# Balancing_FETs.net
KiCad netlist of a schematic drawn in Altium Designer
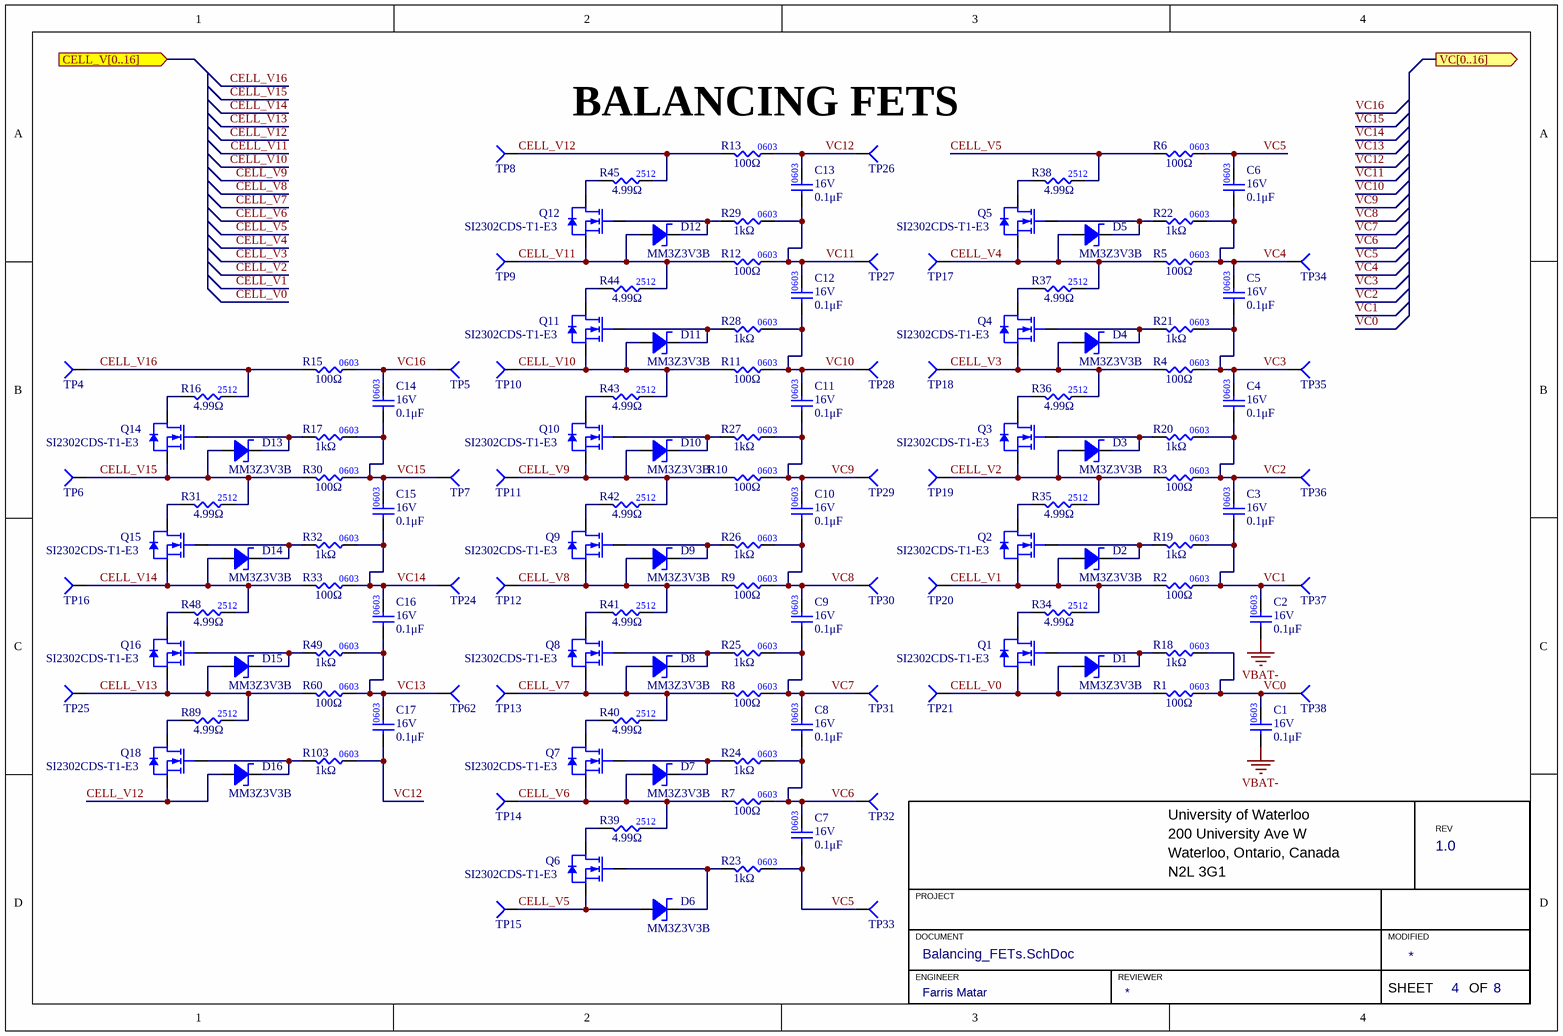
[diagram p0: Balancing_FETs.SchDoc]

(export (version "E")
  (design (tool "Eeschema 10.0.6"))
  (components
    (comp (ref "C1")
      (value "0.1μF")
      (footprint "CAP0603")
      (description "CAP CER 0.1UF 16V X7R 0603")
      (fields (field (name "VOLTAGE RATING") "16V") (field (name "Comment") "CAP_0.1uF_16V_0603"))
      (libsource (lib "Personal_Schematic_Library_2022") (part "CAP_0.1uF_16V_0603"))
    )
    (comp (ref "C2")
      (value "0.1μF")
      (footprint "CAP0603")
      (description "CAP CER 0.1UF 16V X7R 0603")
      (fields (field (name "VOLTAGE RATING") "16V") (field (name "Comment") "CAP_0.1uF_16V_0603"))
      (libsource (lib "Personal_Schematic_Library_2022") (part "CAP_0.1uF_16V_0603"))
    )
    (comp (ref "C3")
      (value "0.1μF")
      (footprint "CAP0603")
      (description "CAP CER 0.1UF 16V X7R 0603")
      (fields (field (name "VOLTAGE RATING") "16V") (field (name "Comment") "CAP_0.1uF_16V_0603"))
      (libsource (lib "Personal_Schematic_Library_2022") (part "CAP_0.1uF_16V_0603"))
    )
    (comp (ref "C4")
      (value "0.1μF")
      (footprint "CAP0603")
      (description "CAP CER 0.1UF 16V X7R 0603")
      (fields (field (name "VOLTAGE RATING") "16V") (field (name "Comment") "CAP_0.1uF_16V_0603"))
      (libsource (lib "Personal_Schematic_Library_2022") (part "CAP_0.1uF_16V_0603"))
    )
    (comp (ref "C5")
      (value "0.1μF")
      (footprint "CAP0603")
      (description "CAP CER 0.1UF 16V X7R 0603")
      (fields (field (name "VOLTAGE RATING") "16V") (field (name "Comment") "CAP_0.1uF_16V_0603"))
      (libsource (lib "Personal_Schematic_Library_2022") (part "CAP_0.1uF_16V_0603"))
    )
    (comp (ref "C6")
      (value "0.1μF")
      (footprint "CAP0603")
      (description "CAP CER 0.1UF 16V X7R 0603")
      (fields (field (name "VOLTAGE RATING") "16V") (field (name "Comment") "CAP_0.1uF_16V_0603"))
      (libsource (lib "Personal_Schematic_Library_2022") (part "CAP_0.1uF_16V_0603"))
    )
    (comp (ref "C7")
      (value "0.1μF")
      (footprint "CAP0603")
      (description "CAP CER 0.1UF 16V X7R 0603")
      (fields (field (name "VOLTAGE RATING") "16V") (field (name "Comment") "CAP_0.1uF_16V_0603"))
      (libsource (lib "Personal_Schematic_Library_2022") (part "CAP_0.1uF_16V_0603"))
    )
    (comp (ref "C8")
      (value "0.1μF")
      (footprint "CAP0603")
      (description "CAP CER 0.1UF 16V X7R 0603")
      (fields (field (name "VOLTAGE RATING") "16V") (field (name "Comment") "CAP_0.1uF_16V_0603"))
      (libsource (lib "Personal_Schematic_Library_2022") (part "CAP_0.1uF_16V_0603"))
    )
    (comp (ref "C9")
      (value "0.1μF")
      (footprint "CAP0603")
      (description "CAP CER 0.1UF 16V X7R 0603")
      (fields (field (name "VOLTAGE RATING") "16V") (field (name "Comment") "CAP_0.1uF_16V_0603"))
      (libsource (lib "Personal_Schematic_Library_2022") (part "CAP_0.1uF_16V_0603"))
    )
    (comp (ref "C10")
      (value "0.1μF")
      (footprint "CAP0603")
      (description "CAP CER 0.1UF 16V X7R 0603")
      (fields (field (name "VOLTAGE RATING") "16V") (field (name "Comment") "CAP_0.1uF_16V_0603"))
      (libsource (lib "Personal_Schematic_Library_2022") (part "CAP_0.1uF_16V_0603"))
    )
    (comp (ref "C11")
      (value "0.1μF")
      (footprint "CAP0603")
      (description "CAP CER 0.1UF 16V X7R 0603")
      (fields (field (name "VOLTAGE RATING") "16V") (field (name "Comment") "CAP_0.1uF_16V_0603"))
      (libsource (lib "Personal_Schematic_Library_2022") (part "CAP_0.1uF_16V_0603"))
    )
    (comp (ref "C12")
      (value "0.1μF")
      (footprint "CAP0603")
      (description "CAP CER 0.1UF 16V X7R 0603")
      (fields (field (name "VOLTAGE RATING") "16V") (field (name "Comment") "CAP_0.1uF_16V_0603"))
      (libsource (lib "Personal_Schematic_Library_2022") (part "CAP_0.1uF_16V_0603"))
    )
    (comp (ref "C13")
      (value "0.1μF")
      (footprint "CAP0603")
      (description "CAP CER 0.1UF 16V X7R 0603")
      (fields (field (name "VOLTAGE RATING") "16V") (field (name "Comment") "CAP_0.1uF_16V_0603"))
      (libsource (lib "Personal_Schematic_Library_2022") (part "CAP_0.1uF_16V_0603"))
    )
    (comp (ref "C14")
      (value "0.1μF")
      (footprint "CAP0603")
      (description "CAP CER 0.1UF 16V X7R 0603")
      (fields (field (name "VOLTAGE RATING") "16V") (field (name "Comment") "CAP_0.1uF_16V_0603"))
      (libsource (lib "Personal_Schematic_Library_2022") (part "CAP_0.1uF_16V_0603"))
    )
    (comp (ref "C15")
      (value "0.1μF")
      (footprint "CAP0603")
      (description "CAP CER 0.1UF 16V X7R 0603")
      (fields (field (name "VOLTAGE RATING") "16V") (field (name "Comment") "CAP_0.1uF_16V_0603"))
      (libsource (lib "Personal_Schematic_Library_2022") (part "CAP_0.1uF_16V_0603"))
    )
    (comp (ref "C16")
      (value "0.1μF")
      (footprint "CAP0603")
      (description "CAP CER 0.1UF 16V X7R 0603")
      (fields (field (name "VOLTAGE RATING") "16V") (field (name "Comment") "CAP_0.1uF_16V_0603"))
      (libsource (lib "Personal_Schematic_Library_2022") (part "CAP_0.1uF_16V_0603"))
    )
    (comp (ref "C17")
      (value "0.1μF")
      (footprint "CAP0603")
      (description "CAP CER 0.1UF 16V X7R 0603")
      (fields (field (name "VOLTAGE RATING") "16V") (field (name "Comment") "CAP_0.1uF_16V_0603"))
      (libsource (lib "Personal_Schematic_Library_2022") (part "CAP_0.1uF_16V_0603"))
    )
    (comp (ref "D1")
      (value "DIO_ZENER_3V3")
      (footprint "DIO_ZENER_3V3")
      (description "DIODE ZENER 3.3V 200mW SOD323F")
      (fields (field (name "MANUFACTURER PART NUMBER 1") "MM3Z3V3B"))
      (libsource (lib "Personal_Schematic_Library_2022") (part "DIO_ZENER_3V3"))
    )
    (comp (ref "D2")
      (value "DIO_ZENER_3V3")
      (footprint "DIO_ZENER_3V3")
      (description "DIODE ZENER 3.3V 200mW SOD323F")
      (fields (field (name "MANUFACTURER PART NUMBER 1") "MM3Z3V3B"))
      (libsource (lib "Personal_Schematic_Library_2022") (part "DIO_ZENER_3V3"))
    )
    (comp (ref "D3")
      (value "DIO_ZENER_3V3")
      (footprint "DIO_ZENER_3V3")
      (description "DIODE ZENER 3.3V 200mW SOD323F")
      (fields (field (name "MANUFACTURER PART NUMBER 1") "MM3Z3V3B"))
      (libsource (lib "Personal_Schematic_Library_2022") (part "DIO_ZENER_3V3"))
    )
    (comp (ref "D4")
      (value "DIO_ZENER_3V3")
      (footprint "DIO_ZENER_3V3")
      (description "DIODE ZENER 3.3V 200mW SOD323F")
      (fields (field (name "MANUFACTURER PART NUMBER 1") "MM3Z3V3B"))
      (libsource (lib "Personal_Schematic_Library_2022") (part "DIO_ZENER_3V3"))
    )
    (comp (ref "D5")
      (value "DIO_ZENER_3V3")
      (footprint "DIO_ZENER_3V3")
      (description "DIODE ZENER 3.3V 200mW SOD323F")
      (fields (field (name "MANUFACTURER PART NUMBER 1") "MM3Z3V3B"))
      (libsource (lib "Personal_Schematic_Library_2022") (part "DIO_ZENER_3V3"))
    )
    (comp (ref "D6")
      (value "DIO_ZENER_3V3")
      (footprint "DIO_ZENER_3V3")
      (description "DIODE ZENER 3.3V 200mW SOD323F")
      (fields (field (name "MANUFACTURER PART NUMBER 1") "MM3Z3V3B"))
      (libsource (lib "Personal_Schematic_Library_2022") (part "DIO_ZENER_3V3"))
    )
    (comp (ref "D7")
      (value "DIO_ZENER_3V3")
      (footprint "DIO_ZENER_3V3")
      (description "DIODE ZENER 3.3V 200mW SOD323F")
      (fields (field (name "MANUFACTURER PART NUMBER 1") "MM3Z3V3B"))
      (libsource (lib "Personal_Schematic_Library_2022") (part "DIO_ZENER_3V3"))
    )
    (comp (ref "D8")
      (value "DIO_ZENER_3V3")
      (footprint "DIO_ZENER_3V3")
      (description "DIODE ZENER 3.3V 200mW SOD323F")
      (fields (field (name "MANUFACTURER PART NUMBER 1") "MM3Z3V3B"))
      (libsource (lib "Personal_Schematic_Library_2022") (part "DIO_ZENER_3V3"))
    )
    (comp (ref "D9")
      (value "DIO_ZENER_3V3")
      (footprint "DIO_ZENER_3V3")
      (description "DIODE ZENER 3.3V 200mW SOD323F")
      (fields (field (name "MANUFACTURER PART NUMBER 1") "MM3Z3V3B"))
      (libsource (lib "Personal_Schematic_Library_2022") (part "DIO_ZENER_3V3"))
    )
    (comp (ref "D10")
      (value "DIO_ZENER_3V3")
      (footprint "DIO_ZENER_3V3")
      (description "DIODE ZENER 3.3V 200mW SOD323F")
      (fields (field (name "MANUFACTURER PART NUMBER 1") "MM3Z3V3B"))
      (libsource (lib "Personal_Schematic_Library_2022") (part "DIO_ZENER_3V3"))
    )
    (comp (ref "D11")
      (value "DIO_ZENER_3V3")
      (footprint "DIO_ZENER_3V3")
      (description "DIODE ZENER 3.3V 200mW SOD323F")
      (fields (field (name "MANUFACTURER PART NUMBER 1") "MM3Z3V3B"))
      (libsource (lib "Personal_Schematic_Library_2022") (part "DIO_ZENER_3V3"))
    )
    (comp (ref "D12")
      (value "DIO_ZENER_3V3")
      (footprint "DIO_ZENER_3V3")
      (description "DIODE ZENER 3.3V 200mW SOD323F")
      (fields (field (name "MANUFACTURER PART NUMBER 1") "MM3Z3V3B"))
      (libsource (lib "Personal_Schematic_Library_2022") (part "DIO_ZENER_3V3"))
    )
    (comp (ref "D13")
      (value "DIO_ZENER_3V3")
      (footprint "DIO_ZENER_3V3")
      (description "DIODE ZENER 3.3V 200mW SOD323F")
      (fields (field (name "MANUFACTURER PART NUMBER 1") "MM3Z3V3B"))
      (libsource (lib "Personal_Schematic_Library_2022") (part "DIO_ZENER_3V3"))
    )
    (comp (ref "D14")
      (value "DIO_ZENER_3V3")
      (footprint "DIO_ZENER_3V3")
      (description "DIODE ZENER 3.3V 200mW SOD323F")
      (fields (field (name "MANUFACTURER PART NUMBER 1") "MM3Z3V3B"))
      (libsource (lib "Personal_Schematic_Library_2022") (part "DIO_ZENER_3V3"))
    )
    (comp (ref "D15")
      (value "DIO_ZENER_3V3")
      (footprint "DIO_ZENER_3V3")
      (description "DIODE ZENER 3.3V 200mW SOD323F")
      (fields (field (name "MANUFACTURER PART NUMBER 1") "MM3Z3V3B"))
      (libsource (lib "Personal_Schematic_Library_2022") (part "DIO_ZENER_3V3"))
    )
    (comp (ref "D16")
      (value "DIO_ZENER_3V3")
      (footprint "DIO_ZENER_3V3")
      (description "DIODE ZENER 3.3V 200mW SOD323F")
      (fields (field (name "MANUFACTURER PART NUMBER 1") "MM3Z3V3B"))
      (libsource (lib "Personal_Schematic_Library_2022") (part "DIO_ZENER_3V3"))
    )
    (comp (ref "Q1")
      (value "NMOS_20V_6A")
      (footprint "SOT23-3")
      (description "MOSFET N-CH 20V 2.6A SOT23-3")
      (fields (field (name "MANUFACTURER PART NUMBER 1") "SI2302CDS-T1-E3"))
      (libsource (lib "Personal_Schematic_Library_2022") (part "NMOS_20V_2.6A"))
    )
    (comp (ref "Q2")
      (value "NMOS_20V_6A")
      (footprint "SOT23-3")
      (description "MOSFET N-CH 20V 2.6A SOT23-3")
      (fields (field (name "MANUFACTURER PART NUMBER 1") "SI2302CDS-T1-E3"))
      (libsource (lib "Personal_Schematic_Library_2022") (part "NMOS_20V_2.6A"))
    )
    (comp (ref "Q3")
      (value "NMOS_20V_6A")
      (footprint "SOT23-3")
      (description "MOSFET N-CH 20V 2.6A SOT23-3")
      (fields (field (name "MANUFACTURER PART NUMBER 1") "SI2302CDS-T1-E3"))
      (libsource (lib "Personal_Schematic_Library_2022") (part "NMOS_20V_2.6A"))
    )
    (comp (ref "Q4")
      (value "NMOS_20V_6A")
      (footprint "SOT23-3")
      (description "MOSFET N-CH 20V 2.6A SOT23-3")
      (fields (field (name "MANUFACTURER PART NUMBER 1") "SI2302CDS-T1-E3"))
      (libsource (lib "Personal_Schematic_Library_2022") (part "NMOS_20V_2.6A"))
    )
    (comp (ref "Q5")
      (value "NMOS_20V_6A")
      (footprint "SOT23-3")
      (description "MOSFET N-CH 20V 2.6A SOT23-3")
      (fields (field (name "MANUFACTURER PART NUMBER 1") "SI2302CDS-T1-E3"))
      (libsource (lib "Personal_Schematic_Library_2022") (part "NMOS_20V_2.6A"))
    )
    (comp (ref "Q6")
      (value "NMOS_20V_6A")
      (footprint "SOT23-3")
      (description "MOSFET N-CH 20V 2.6A SOT23-3")
      (fields (field (name "MANUFACTURER PART NUMBER 1") "SI2302CDS-T1-E3"))
      (libsource (lib "Personal_Schematic_Library_2022") (part "NMOS_20V_2.6A"))
    )
    (comp (ref "Q7")
      (value "NMOS_20V_6A")
      (footprint "SOT23-3")
      (description "MOSFET N-CH 20V 2.6A SOT23-3")
      (fields (field (name "MANUFACTURER PART NUMBER 1") "SI2302CDS-T1-E3"))
      (libsource (lib "Personal_Schematic_Library_2022") (part "NMOS_20V_2.6A"))
    )
    (comp (ref "Q8")
      (value "NMOS_20V_6A")
      (footprint "SOT23-3")
      (description "MOSFET N-CH 20V 2.6A SOT23-3")
      (fields (field (name "MANUFACTURER PART NUMBER 1") "SI2302CDS-T1-E3"))
      (libsource (lib "Personal_Schematic_Library_2022") (part "NMOS_20V_2.6A"))
    )
    (comp (ref "Q9")
      (value "NMOS_20V_6A")
      (footprint "SOT23-3")
      (description "MOSFET N-CH 20V 2.6A SOT23-3")
      (fields (field (name "MANUFACTURER PART NUMBER 1") "SI2302CDS-T1-E3"))
      (libsource (lib "Personal_Schematic_Library_2022") (part "NMOS_20V_2.6A"))
    )
    (comp (ref "Q10")
      (value "NMOS_20V_6A")
      (footprint "SOT23-3")
      (description "MOSFET N-CH 20V 2.6A SOT23-3")
      (fields (field (name "MANUFACTURER PART NUMBER 1") "SI2302CDS-T1-E3"))
      (libsource (lib "Personal_Schematic_Library_2022") (part "NMOS_20V_2.6A"))
    )
    (comp (ref "Q11")
      (value "NMOS_20V_6A")
      (footprint "SOT23-3")
      (description "MOSFET N-CH 20V 2.6A SOT23-3")
      (fields (field (name "MANUFACTURER PART NUMBER 1") "SI2302CDS-T1-E3"))
      (libsource (lib "Personal_Schematic_Library_2022") (part "NMOS_20V_2.6A"))
    )
    (comp (ref "Q12")
      (value "NMOS_20V_6A")
      (footprint "SOT23-3")
      (description "MOSFET N-CH 20V 2.6A SOT23-3")
      (fields (field (name "MANUFACTURER PART NUMBER 1") "SI2302CDS-T1-E3"))
      (libsource (lib "Personal_Schematic_Library_2022") (part "NMOS_20V_2.6A"))
    )
    (comp (ref "Q14")
      (value "NMOS_20V_6A")
      (footprint "SOT23-3")
      (description "MOSFET N-CH 20V 2.6A SOT23-3")
      (fields (field (name "MANUFACTURER PART NUMBER 1") "SI2302CDS-T1-E3"))
      (libsource (lib "Personal_Schematic_Library_2022") (part "NMOS_20V_2.6A"))
    )
    (comp (ref "Q15")
      (value "NMOS_20V_6A")
      (footprint "SOT23-3")
      (description "MOSFET N-CH 20V 2.6A SOT23-3")
      (fields (field (name "MANUFACTURER PART NUMBER 1") "SI2302CDS-T1-E3"))
      (libsource (lib "Personal_Schematic_Library_2022") (part "NMOS_20V_2.6A"))
    )
    (comp (ref "Q16")
      (value "NMOS_20V_6A")
      (footprint "SOT23-3")
      (description "MOSFET N-CH 20V 2.6A SOT23-3")
      (fields (field (name "MANUFACTURER PART NUMBER 1") "SI2302CDS-T1-E3"))
      (libsource (lib "Personal_Schematic_Library_2022") (part "NMOS_20V_2.6A"))
    )
    (comp (ref "Q18")
      (value "NMOS_20V_6A")
      (footprint "SOT23-3")
      (description "MOSFET N-CH 20V 2.6A SOT23-3")
      (fields (field (name "MANUFACTURER PART NUMBER 1") "SI2302CDS-T1-E3"))
      (libsource (lib "Personal_Schematic_Library_2022") (part "NMOS_20V_2.6A"))
    )
    (comp (ref "R1")
      (value "100Ω")
      (footprint "RES0603")
      (description "RES 100 OHM 1% 1/10W 0603")
      (fields (field (name "Comment") "RES_100Ω_0603_1%"))
      (libsource (lib "Personal_Schematic_Library_2022") (part "RES_100Ω_0603_1%"))
    )
    (comp (ref "R2")
      (value "100Ω")
      (footprint "RES0603")
      (description "RES 100 OHM 1% 1/10W 0603")
      (fields (field (name "Comment") "RES_100Ω_0603_1%"))
      (libsource (lib "Personal_Schematic_Library_2022") (part "RES_100Ω_0603_1%"))
    )
    (comp (ref "R3")
      (value "100Ω")
      (footprint "RES0603")
      (description "RES 100 OHM 1% 1/10W 0603")
      (fields (field (name "Comment") "RES_100Ω_0603_1%"))
      (libsource (lib "Personal_Schematic_Library_2022") (part "RES_100Ω_0603_1%"))
    )
    (comp (ref "R4")
      (value "100Ω")
      (footprint "RES0603")
      (description "RES 100 OHM 1% 1/10W 0603")
      (fields (field (name "Comment") "RES_100Ω_0603_1%"))
      (libsource (lib "Personal_Schematic_Library_2022") (part "RES_100Ω_0603_1%"))
    )
    (comp (ref "R5")
      (value "100Ω")
      (footprint "RES0603")
      (description "RES 100 OHM 1% 1/10W 0603")
      (fields (field (name "Comment") "RES_100Ω_0603_1%"))
      (libsource (lib "Personal_Schematic_Library_2022") (part "RES_100Ω_0603_1%"))
    )
    (comp (ref "R6")
      (value "100Ω")
      (footprint "RES0603")
      (description "RES 100 OHM 1% 1/10W 0603")
      (fields (field (name "Comment") "RES_100Ω_0603_1%"))
      (libsource (lib "Personal_Schematic_Library_2022") (part "RES_100Ω_0603_1%"))
    )
    (comp (ref "R7")
      (value "100Ω")
      (footprint "RES0603")
      (description "RES 100 OHM 1% 1/10W 0603")
      (fields (field (name "Comment") "RES_100Ω_0603_1%"))
      (libsource (lib "Personal_Schematic_Library_2022") (part "RES_100Ω_0603_1%"))
    )
    (comp (ref "R8")
      (value "100Ω")
      (footprint "RES0603")
      (description "RES 100 OHM 1% 1/10W 0603")
      (fields (field (name "Comment") "RES_100Ω_0603_1%"))
      (libsource (lib "Personal_Schematic_Library_2022") (part "RES_100Ω_0603_1%"))
    )
    (comp (ref "R9")
      (value "100Ω")
      (footprint "RES0603")
      (description "RES 100 OHM 1% 1/10W 0603")
      (fields (field (name "Comment") "RES_100Ω_0603_1%"))
      (libsource (lib "Personal_Schematic_Library_2022") (part "RES_100Ω_0603_1%"))
    )
    (comp (ref "R10")
      (value "100Ω")
      (footprint "RES0603")
      (description "RES 100 OHM 1% 1/10W 0603")
      (fields (field (name "Comment") "RES_100Ω_0603_1%"))
      (libsource (lib "Personal_Schematic_Library_2022") (part "RES_100Ω_0603_1%"))
    )
    (comp (ref "R11")
      (value "100Ω")
      (footprint "RES0603")
      (description "RES 100 OHM 1% 1/10W 0603")
      (fields (field (name "Comment") "RES_100Ω_0603_1%"))
      (libsource (lib "Personal_Schematic_Library_2022") (part "RES_100Ω_0603_1%"))
    )
    (comp (ref "R12")
      (value "100Ω")
      (footprint "RES0603")
      (description "RES 100 OHM 1% 1/10W 0603")
      (fields (field (name "Comment") "RES_100Ω_0603_1%"))
      (libsource (lib "Personal_Schematic_Library_2022") (part "RES_100Ω_0603_1%"))
    )
    (comp (ref "R13")
      (value "100Ω")
      (footprint "RES0603")
      (description "RES 100 OHM 1% 1/10W 0603")
      (fields (field (name "Comment") "RES_100Ω_0603_1%"))
      (libsource (lib "Personal_Schematic_Library_2022") (part "RES_100Ω_0603_1%"))
    )
    (comp (ref "R15")
      (value "100Ω")
      (footprint "RES0603")
      (description "RES 100 OHM 1% 1/10W 0603")
      (fields (field (name "Comment") "RES_100Ω_0603_1%"))
      (libsource (lib "Personal_Schematic_Library_2022") (part "RES_100Ω_0603_1%"))
    )
    (comp (ref "R16")
      (value "4.99Ω")
      (footprint "RES2512")
      (description "RES 4.99 OHM 1% 2W 2512")
      (fields (field (name "Comment") "RES_4.99Ω_2512_1%"))
      (libsource (lib "Personal_Schematic_Library_2022") (part "RES_4.99Ω_2512_1%"))
    )
    (comp (ref "R17")
      (value "1kΩ")
      (footprint "RES0603")
      (description "RES 1K OHM 1% 1/8W 0603")
      (fields (field (name "Comment") "RES_1kΩ_0603_1%"))
      (libsource (lib "Personal_Schematic_Library_2022") (part "RES_1kΩ_0603_1%"))
    )
    (comp (ref "R18")
      (value "1kΩ")
      (footprint "RES0603")
      (description "RES 1K OHM 1% 1/8W 0603")
      (fields (field (name "Comment") "RES_1kΩ_0603_1%"))
      (libsource (lib "Personal_Schematic_Library_2022") (part "RES_1kΩ_0603_1%"))
    )
    (comp (ref "R19")
      (value "1kΩ")
      (footprint "RES0603")
      (description "RES 1K OHM 1% 1/8W 0603")
      (fields (field (name "Comment") "RES_1kΩ_0603_1%"))
      (libsource (lib "Personal_Schematic_Library_2022") (part "RES_1kΩ_0603_1%"))
    )
    (comp (ref "R20")
      (value "1kΩ")
      (footprint "RES0603")
      (description "RES 1K OHM 1% 1/8W 0603")
      (fields (field (name "Comment") "RES_1kΩ_0603_1%"))
      (libsource (lib "Personal_Schematic_Library_2022") (part "RES_1kΩ_0603_1%"))
    )
    (comp (ref "R21")
      (value "1kΩ")
      (footprint "RES0603")
      (description "RES 1K OHM 1% 1/8W 0603")
      (fields (field (name "Comment") "RES_1kΩ_0603_1%"))
      (libsource (lib "Personal_Schematic_Library_2022") (part "RES_1kΩ_0603_1%"))
    )
    (comp (ref "R22")
      (value "1kΩ")
      (footprint "RES0603")
      (description "RES 1K OHM 1% 1/8W 0603")
      (fields (field (name "Comment") "RES_1kΩ_0603_1%"))
      (libsource (lib "Personal_Schematic_Library_2022") (part "RES_1kΩ_0603_1%"))
    )
    (comp (ref "R23")
      (value "1kΩ")
      (footprint "RES0603")
      (description "RES 1K OHM 1% 1/8W 0603")
      (fields (field (name "Comment") "RES_1kΩ_0603_1%"))
      (libsource (lib "Personal_Schematic_Library_2022") (part "RES_1kΩ_0603_1%"))
    )
    (comp (ref "R24")
      (value "1kΩ")
      (footprint "RES0603")
      (description "RES 1K OHM 1% 1/8W 0603")
      (fields (field (name "Comment") "RES_1kΩ_0603_1%"))
      (libsource (lib "Personal_Schematic_Library_2022") (part "RES_1kΩ_0603_1%"))
    )
    (comp (ref "R25")
      (value "1kΩ")
      (footprint "RES0603")
      (description "RES 1K OHM 1% 1/8W 0603")
      (fields (field (name "Comment") "RES_1kΩ_0603_1%"))
      (libsource (lib "Personal_Schematic_Library_2022") (part "RES_1kΩ_0603_1%"))
    )
    (comp (ref "R26")
      (value "1kΩ")
      (footprint "RES0603")
      (description "RES 1K OHM 1% 1/8W 0603")
      (fields (field (name "Comment") "RES_1kΩ_0603_1%"))
      (libsource (lib "Personal_Schematic_Library_2022") (part "RES_1kΩ_0603_1%"))
    )
    (comp (ref "R27")
      (value "1kΩ")
      (footprint "RES0603")
      (description "RES 1K OHM 1% 1/8W 0603")
      (fields (field (name "Comment") "RES_1kΩ_0603_1%"))
      (libsource (lib "Personal_Schematic_Library_2022") (part "RES_1kΩ_0603_1%"))
    )
    (comp (ref "R28")
      (value "1kΩ")
      (footprint "RES0603")
      (description "RES 1K OHM 1% 1/8W 0603")
      (fields (field (name "Comment") "RES_1kΩ_0603_1%"))
      (libsource (lib "Personal_Schematic_Library_2022") (part "RES_1kΩ_0603_1%"))
    )
    (comp (ref "R29")
      (value "1kΩ")
      (footprint "RES0603")
      (description "RES 1K OHM 1% 1/8W 0603")
      (fields (field (name "Comment") "RES_1kΩ_0603_1%"))
      (libsource (lib "Personal_Schematic_Library_2022") (part "RES_1kΩ_0603_1%"))
    )
    (comp (ref "R30")
      (value "100Ω")
      (footprint "RES0603")
      (description "RES 100 OHM 1% 1/10W 0603")
      (fields (field (name "Comment") "RES_100Ω_0603_1%"))
      (libsource (lib "Personal_Schematic_Library_2022") (part "RES_100Ω_0603_1%"))
    )
    (comp (ref "R31")
      (value "4.99Ω")
      (footprint "RES2512")
      (description "RES 4.99 OHM 1% 2W 2512")
      (fields (field (name "Comment") "RES_4.99Ω_2512_1%"))
      (libsource (lib "Personal_Schematic_Library_2022") (part "RES_4.99Ω_2512_1%"))
    )
    (comp (ref "R32")
      (value "1kΩ")
      (footprint "RES0603")
      (description "RES 1K OHM 1% 1/8W 0603")
      (fields (field (name "Comment") "RES_1kΩ_0603_1%"))
      (libsource (lib "Personal_Schematic_Library_2022") (part "RES_1kΩ_0603_1%"))
    )
    (comp (ref "R33")
      (value "100Ω")
      (footprint "RES0603")
      (description "RES 100 OHM 1% 1/10W 0603")
      (fields (field (name "Comment") "RES_100Ω_0603_1%"))
      (libsource (lib "Personal_Schematic_Library_2022") (part "RES_100Ω_0603_1%"))
    )
    (comp (ref "R34")
      (value "4.99Ω")
      (footprint "RES2512")
      (description "RES 4.99 OHM 1% 2W 2512")
      (fields (field (name "Comment") "RES_4.99Ω_2512_1%"))
      (libsource (lib "Personal_Schematic_Library_2022") (part "RES_4.99Ω_2512_1%"))
    )
    (comp (ref "R35")
      (value "4.99Ω")
      (footprint "RES2512")
      (description "RES 4.99 OHM 1% 2W 2512")
      (fields (field (name "Comment") "RES_4.99Ω_2512_1%"))
      (libsource (lib "Personal_Schematic_Library_2022") (part "RES_4.99Ω_2512_1%"))
    )
    (comp (ref "R36")
      (value "4.99Ω")
      (footprint "RES2512")
      (description "RES 4.99 OHM 1% 2W 2512")
      (fields (field (name "Comment") "RES_4.99Ω_2512_1%"))
      (libsource (lib "Personal_Schematic_Library_2022") (part "RES_4.99Ω_2512_1%"))
    )
    (comp (ref "R37")
      (value "4.99Ω")
      (footprint "RES2512")
      (description "RES 4.99 OHM 1% 2W 2512")
      (fields (field (name "Comment") "RES_4.99Ω_2512_1%"))
      (libsource (lib "Personal_Schematic_Library_2022") (part "RES_4.99Ω_2512_1%"))
    )
    (comp (ref "R38")
      (value "4.99Ω")
      (footprint "RES2512")
      (description "RES 4.99 OHM 1% 2W 2512")
      (fields (field (name "Comment") "RES_4.99Ω_2512_1%"))
      (libsource (lib "Personal_Schematic_Library_2022") (part "RES_4.99Ω_2512_1%"))
    )
    (comp (ref "R39")
      (value "4.99Ω")
      (footprint "RES2512")
      (description "RES 4.99 OHM 1% 2W 2512")
      (fields (field (name "Comment") "RES_4.99Ω_2512_1%"))
      (libsource (lib "Personal_Schematic_Library_2022") (part "RES_4.99Ω_2512_1%"))
    )
    (comp (ref "R40")
      (value "4.99Ω")
      (footprint "RES2512")
      (description "RES 4.99 OHM 1% 2W 2512")
      (fields (field (name "Comment") "RES_4.99Ω_2512_1%"))
      (libsource (lib "Personal_Schematic_Library_2022") (part "RES_4.99Ω_2512_1%"))
    )
    (comp (ref "R41")
      (value "4.99Ω")
      (footprint "RES2512")
      (description "RES 4.99 OHM 1% 2W 2512")
      (fields (field (name "Comment") "RES_4.99Ω_2512_1%"))
      (libsource (lib "Personal_Schematic_Library_2022") (part "RES_4.99Ω_2512_1%"))
    )
    (comp (ref "R42")
      (value "4.99Ω")
      (footprint "RES2512")
      (description "RES 4.99 OHM 1% 2W 2512")
      (fields (field (name "Comment") "RES_4.99Ω_2512_1%"))
      (libsource (lib "Personal_Schematic_Library_2022") (part "RES_4.99Ω_2512_1%"))
    )
    (comp (ref "R43")
      (value "4.99Ω")
      (footprint "RES2512")
      (description "RES 4.99 OHM 1% 2W 2512")
      (fields (field (name "Comment") "RES_4.99Ω_2512_1%"))
      (libsource (lib "Personal_Schematic_Library_2022") (part "RES_4.99Ω_2512_1%"))
    )
    (comp (ref "R44")
      (value "4.99Ω")
      (footprint "RES2512")
      (description "RES 4.99 OHM 1% 2W 2512")
      (fields (field (name "Comment") "RES_4.99Ω_2512_1%"))
      (libsource (lib "Personal_Schematic_Library_2022") (part "RES_4.99Ω_2512_1%"))
    )
    (comp (ref "R45")
      (value "4.99Ω")
      (footprint "RES2512")
      (description "RES 4.99 OHM 1% 2W 2512")
      (fields (field (name "Comment") "RES_4.99Ω_2512_1%"))
      (libsource (lib "Personal_Schematic_Library_2022") (part "RES_4.99Ω_2512_1%"))
    )
    (comp (ref "R48")
      (value "4.99Ω")
      (footprint "RES2512")
      (description "RES 4.99 OHM 1% 2W 2512")
      (fields (field (name "Comment") "RES_4.99Ω_2512_1%"))
      (libsource (lib "Personal_Schematic_Library_2022") (part "RES_4.99Ω_2512_1%"))
    )
    (comp (ref "R49")
      (value "1kΩ")
      (footprint "RES0603")
      (description "RES 1K OHM 1% 1/8W 0603")
      (fields (field (name "Comment") "RES_1kΩ_0603_1%"))
      (libsource (lib "Personal_Schematic_Library_2022") (part "RES_1kΩ_0603_1%"))
    )
    (comp (ref "R60")
      (value "100Ω")
      (footprint "RES0603")
      (description "RES 100 OHM 1% 1/10W 0603")
      (fields (field (name "Comment") "RES_100Ω_0603_1%"))
      (libsource (lib "Personal_Schematic_Library_2022") (part "RES_100Ω_0603_1%"))
    )
    (comp (ref "R89")
      (value "4.99Ω")
      (footprint "RES2512")
      (description "RES 4.99 OHM 1% 2W 2512")
      (fields (field (name "Comment") "RES_4.99Ω_2512_1%"))
      (libsource (lib "Personal_Schematic_Library_2022") (part "RES_4.99Ω_2512_1%"))
    )
    (comp (ref "R103")
      (value "1kΩ")
      (footprint "RES0603")
      (description "RES 1K OHM 1% 1/8W 0603")
      (fields (field (name "Comment") "RES_1kΩ_0603_1%"))
      (libsource (lib "Personal_Schematic_Library_2022") (part "RES_1kΩ_0603_1%"))
    )
    (comp (ref "TP4")
      (value "TESTPOINT_1MM_SQUARE")
      (footprint "TESTPOINT_SQUARE_1MM")
      (description "TESTPOINT 1MM SQUARE")
      (libsource (lib "Personal_Schematic_Library_2022") (part "TESTPOINT_1MM_SQUARE"))
    )
    (comp (ref "TP5")
      (value "TESTPOINT_1MM_SQUARE")
      (footprint "TESTPOINT_SQUARE_1MM")
      (description "TESTPOINT 1MM SQUARE")
      (libsource (lib "Personal_Schematic_Library_2022") (part "TESTPOINT_1MM_SQUARE"))
    )
    (comp (ref "TP6")
      (value "TESTPOINT_1MM_SQUARE")
      (footprint "TESTPOINT_SQUARE_1MM")
      (description "TESTPOINT 1MM SQUARE")
      (libsource (lib "Personal_Schematic_Library_2022") (part "TESTPOINT_1MM_SQUARE"))
    )
    (comp (ref "TP7")
      (value "TESTPOINT_1MM_SQUARE")
      (footprint "TESTPOINT_SQUARE_1MM")
      (description "TESTPOINT 1MM SQUARE")
      (libsource (lib "Personal_Schematic_Library_2022") (part "TESTPOINT_1MM_SQUARE"))
    )
    (comp (ref "TP8")
      (value "TESTPOINT_1MM_SQUARE")
      (footprint "TESTPOINT_SQUARE_1MM")
      (description "TESTPOINT 1MM SQUARE")
      (libsource (lib "Personal_Schematic_Library_2022") (part "TESTPOINT_1MM_SQUARE"))
    )
    (comp (ref "TP9")
      (value "TESTPOINT_1MM_SQUARE")
      (footprint "TESTPOINT_SQUARE_1MM")
      (description "TESTPOINT 1MM SQUARE")
      (libsource (lib "Personal_Schematic_Library_2022") (part "TESTPOINT_1MM_SQUARE"))
    )
    (comp (ref "TP10")
      (value "TESTPOINT_1MM_SQUARE")
      (footprint "TESTPOINT_SQUARE_1MM")
      (description "TESTPOINT 1MM SQUARE")
      (libsource (lib "Personal_Schematic_Library_2022") (part "TESTPOINT_1MM_SQUARE"))
    )
    (comp (ref "TP11")
      (value "TESTPOINT_1MM_SQUARE")
      (footprint "TESTPOINT_SQUARE_1MM")
      (description "TESTPOINT 1MM SQUARE")
      (libsource (lib "Personal_Schematic_Library_2022") (part "TESTPOINT_1MM_SQUARE"))
    )
    (comp (ref "TP12")
      (value "TESTPOINT_1MM_SQUARE")
      (footprint "TESTPOINT_SQUARE_1MM")
      (description "TESTPOINT 1MM SQUARE")
      (libsource (lib "Personal_Schematic_Library_2022") (part "TESTPOINT_1MM_SQUARE"))
    )
    (comp (ref "TP13")
      (value "TESTPOINT_1MM_SQUARE")
      (footprint "TESTPOINT_SQUARE_1MM")
      (description "TESTPOINT 1MM SQUARE")
      (libsource (lib "Personal_Schematic_Library_2022") (part "TESTPOINT_1MM_SQUARE"))
    )
    (comp (ref "TP14")
      (value "TESTPOINT_1MM_SQUARE")
      (footprint "TESTPOINT_SQUARE_1MM")
      (description "TESTPOINT 1MM SQUARE")
      (libsource (lib "Personal_Schematic_Library_2022") (part "TESTPOINT_1MM_SQUARE"))
    )
    (comp (ref "TP15")
      (value "TESTPOINT_1MM_SQUARE")
      (footprint "TESTPOINT_SQUARE_1MM")
      (description "TESTPOINT 1MM SQUARE")
      (libsource (lib "Personal_Schematic_Library_2022") (part "TESTPOINT_1MM_SQUARE"))
    )
    (comp (ref "TP16")
      (value "TESTPOINT_1MM_SQUARE")
      (footprint "TESTPOINT_SQUARE_1MM")
      (description "TESTPOINT 1MM SQUARE")
      (libsource (lib "Personal_Schematic_Library_2022") (part "TESTPOINT_1MM_SQUARE"))
    )
    (comp (ref "TP17")
      (value "TESTPOINT_1MM_SQUARE")
      (footprint "TESTPOINT_SQUARE_1MM")
      (description "TESTPOINT 1MM SQUARE")
      (libsource (lib "Personal_Schematic_Library_2022") (part "TESTPOINT_1MM_SQUARE"))
    )
    (comp (ref "TP18")
      (value "TESTPOINT_1MM_SQUARE")
      (footprint "TESTPOINT_SQUARE_1MM")
      (description "TESTPOINT 1MM SQUARE")
      (libsource (lib "Personal_Schematic_Library_2022") (part "TESTPOINT_1MM_SQUARE"))
    )
    (comp (ref "TP19")
      (value "TESTPOINT_1MM_SQUARE")
      (footprint "TESTPOINT_SQUARE_1MM")
      (description "TESTPOINT 1MM SQUARE")
      (libsource (lib "Personal_Schematic_Library_2022") (part "TESTPOINT_1MM_SQUARE"))
    )
    (comp (ref "TP20")
      (value "TESTPOINT_1MM_SQUARE")
      (footprint "TESTPOINT_SQUARE_1MM")
      (description "TESTPOINT 1MM SQUARE")
      (libsource (lib "Personal_Schematic_Library_2022") (part "TESTPOINT_1MM_SQUARE"))
    )
    (comp (ref "TP21")
      (value "TESTPOINT_1MM_SQUARE")
      (footprint "TESTPOINT_SQUARE_1MM")
      (description "TESTPOINT 1MM SQUARE")
      (libsource (lib "Personal_Schematic_Library_2022") (part "TESTPOINT_1MM_SQUARE"))
    )
    (comp (ref "TP24")
      (value "TESTPOINT_1MM_SQUARE")
      (footprint "TESTPOINT_SQUARE_1MM")
      (description "TESTPOINT 1MM SQUARE")
      (libsource (lib "Personal_Schematic_Library_2022") (part "TESTPOINT_1MM_SQUARE"))
    )
    (comp (ref "TP25")
      (value "TESTPOINT_1MM_SQUARE")
      (footprint "TESTPOINT_SQUARE_1MM")
      (description "TESTPOINT 1MM SQUARE")
      (libsource (lib "Personal_Schematic_Library_2022") (part "TESTPOINT_1MM_SQUARE"))
    )
    (comp (ref "TP26")
      (value "TESTPOINT_1MM_SQUARE")
      (footprint "TESTPOINT_SQUARE_1MM")
      (description "TESTPOINT 1MM SQUARE")
      (libsource (lib "Personal_Schematic_Library_2022") (part "TESTPOINT_1MM_SQUARE"))
    )
    (comp (ref "TP27")
      (value "TESTPOINT_1MM_SQUARE")
      (footprint "TESTPOINT_SQUARE_1MM")
      (description "TESTPOINT 1MM SQUARE")
      (libsource (lib "Personal_Schematic_Library_2022") (part "TESTPOINT_1MM_SQUARE"))
    )
    (comp (ref "TP28")
      (value "TESTPOINT_1MM_SQUARE")
      (footprint "TESTPOINT_SQUARE_1MM")
      (description "TESTPOINT 1MM SQUARE")
      (libsource (lib "Personal_Schematic_Library_2022") (part "TESTPOINT_1MM_SQUARE"))
    )
    (comp (ref "TP29")
      (value "TESTPOINT_1MM_SQUARE")
      (footprint "TESTPOINT_SQUARE_1MM")
      (description "TESTPOINT 1MM SQUARE")
      (libsource (lib "Personal_Schematic_Library_2022") (part "TESTPOINT_1MM_SQUARE"))
    )
    (comp (ref "TP30")
      (value "TESTPOINT_1MM_SQUARE")
      (footprint "TESTPOINT_SQUARE_1MM")
      (description "TESTPOINT 1MM SQUARE")
      (libsource (lib "Personal_Schematic_Library_2022") (part "TESTPOINT_1MM_SQUARE"))
    )
    (comp (ref "TP31")
      (value "TESTPOINT_1MM_SQUARE")
      (footprint "TESTPOINT_SQUARE_1MM")
      (description "TESTPOINT 1MM SQUARE")
      (libsource (lib "Personal_Schematic_Library_2022") (part "TESTPOINT_1MM_SQUARE"))
    )
    (comp (ref "TP32")
      (value "TESTPOINT_1MM_SQUARE")
      (footprint "TESTPOINT_SQUARE_1MM")
      (description "TESTPOINT 1MM SQUARE")
      (libsource (lib "Personal_Schematic_Library_2022") (part "TESTPOINT_1MM_SQUARE"))
    )
    (comp (ref "TP33")
      (value "TESTPOINT_1MM_SQUARE")
      (footprint "TESTPOINT_SQUARE_1MM")
      (description "TESTPOINT 1MM SQUARE")
      (libsource (lib "Personal_Schematic_Library_2022") (part "TESTPOINT_1MM_SQUARE"))
    )
    (comp (ref "TP34")
      (value "TESTPOINT_1MM_SQUARE")
      (footprint "TESTPOINT_SQUARE_1MM")
      (description "TESTPOINT 1MM SQUARE")
      (libsource (lib "Personal_Schematic_Library_2022") (part "TESTPOINT_1MM_SQUARE"))
    )
    (comp (ref "TP35")
      (value "TESTPOINT_1MM_SQUARE")
      (footprint "TESTPOINT_SQUARE_1MM")
      (description "TESTPOINT 1MM SQUARE")
      (libsource (lib "Personal_Schematic_Library_2022") (part "TESTPOINT_1MM_SQUARE"))
    )
    (comp (ref "TP36")
      (value "TESTPOINT_1MM_SQUARE")
      (footprint "TESTPOINT_SQUARE_1MM")
      (description "TESTPOINT 1MM SQUARE")
      (libsource (lib "Personal_Schematic_Library_2022") (part "TESTPOINT_1MM_SQUARE"))
    )
    (comp (ref "TP37")
      (value "TESTPOINT_1MM_SQUARE")
      (footprint "TESTPOINT_SQUARE_1MM")
      (description "TESTPOINT 1MM SQUARE")
      (libsource (lib "Personal_Schematic_Library_2022") (part "TESTPOINT_1MM_SQUARE"))
    )
    (comp (ref "TP38")
      (value "TESTPOINT_1MM_SQUARE")
      (footprint "TESTPOINT_SQUARE_1MM")
      (description "TESTPOINT 1MM SQUARE")
      (libsource (lib "Personal_Schematic_Library_2022") (part "TESTPOINT_1MM_SQUARE"))
    )
    (comp (ref "TP62")
      (value "TESTPOINT_1MM_SQUARE")
      (footprint "TESTPOINT_SQUARE_1MM")
      (description "TESTPOINT 1MM SQUARE")
      (libsource (lib "Personal_Schematic_Library_2022") (part "TESTPOINT_1MM_SQUARE"))
    )
  )
  (nets
    (net (code "1") (name "/CELL_V0") (class "Default")
      (node (ref "D1") (pin "1") (pinfunction "Anode_1") (pintype "passive"))
      (node (ref "Q1") (pin "2") (pinfunction "SOURCE_2") (pintype "passive"))
      (node (ref "R1") (pin "1") (pinfunction "1_1") (pintype "passive"))
      (node (ref "TP21") (pin "1") (pinfunction "=value_1") (pintype "passive"))
    )
    (net (code "2") (name "/CELL_V1") (class "Default")
      (node (ref "D2") (pin "1") (pinfunction "Anode_1") (pintype "passive"))
      (node (ref "Q2") (pin "2") (pinfunction "SOURCE_2") (pintype "passive"))
      (node (ref "R2") (pin "1") (pinfunction "1_1") (pintype "passive"))
      (node (ref "R34") (pin "2") (pinfunction "2_2") (pintype "passive"))
      (node (ref "TP20") (pin "1") (pinfunction "=value_1") (pintype "passive"))
    )
    (net (code "3") (name "/CELL_V2") (class "Default")
      (node (ref "D3") (pin "1") (pinfunction "Anode_1") (pintype "passive"))
      (node (ref "Q3") (pin "2") (pinfunction "SOURCE_2") (pintype "passive"))
      (node (ref "R3") (pin "1") (pinfunction "1_1") (pintype "passive"))
      (node (ref "R35") (pin "2") (pinfunction "2_2") (pintype "passive"))
      (node (ref "TP19") (pin "1") (pinfunction "=value_1") (pintype "passive"))
    )
    (net (code "4") (name "/CELL_V3") (class "Default")
      (node (ref "D4") (pin "1") (pinfunction "Anode_1") (pintype "passive"))
      (node (ref "Q4") (pin "2") (pinfunction "SOURCE_2") (pintype "passive"))
      (node (ref "R36") (pin "2") (pinfunction "2_2") (pintype "passive"))
      (node (ref "R4") (pin "1") (pinfunction "1_1") (pintype "passive"))
      (node (ref "TP18") (pin "1") (pinfunction "=value_1") (pintype "passive"))
    )
    (net (code "5") (name "/CELL_V4") (class "Default")
      (node (ref "D5") (pin "1") (pinfunction "Anode_1") (pintype "passive"))
      (node (ref "Q5") (pin "2") (pinfunction "SOURCE_2") (pintype "passive"))
      (node (ref "R37") (pin "2") (pinfunction "2_2") (pintype "passive"))
      (node (ref "R5") (pin "1") (pinfunction "1_1") (pintype "passive"))
      (node (ref "TP17") (pin "1") (pinfunction "=value_1") (pintype "passive"))
    )
    (net (code "6") (name "/CELL_V5") (class "Default")
      (node (ref "D6") (pin "1") (pinfunction "Anode_1") (pintype "passive"))
      (node (ref "Q6") (pin "2") (pinfunction "SOURCE_2") (pintype "passive"))
      (node (ref "R38") (pin "2") (pinfunction "2_2") (pintype "passive"))
      (node (ref "R6") (pin "1") (pinfunction "1_1") (pintype "passive"))
      (node (ref "TP15") (pin "1") (pinfunction "=value_1") (pintype "passive"))
    )
    (net (code "7") (name "/CELL_V6") (class "Default")
      (node (ref "D7") (pin "1") (pinfunction "Anode_1") (pintype "passive"))
      (node (ref "Q7") (pin "2") (pinfunction "SOURCE_2") (pintype "passive"))
      (node (ref "R39") (pin "2") (pinfunction "2_2") (pintype "passive"))
      (node (ref "R7") (pin "1") (pinfunction "1_1") (pintype "passive"))
      (node (ref "TP14") (pin "1") (pinfunction "=value_1") (pintype "passive"))
    )
    (net (code "8") (name "/CELL_V7") (class "Default")
      (node (ref "D8") (pin "1") (pinfunction "Anode_1") (pintype "passive"))
      (node (ref "Q8") (pin "2") (pinfunction "SOURCE_2") (pintype "passive"))
      (node (ref "R40") (pin "2") (pinfunction "2_2") (pintype "passive"))
      (node (ref "R8") (pin "1") (pinfunction "1_1") (pintype "passive"))
      (node (ref "TP13") (pin "1") (pinfunction "=value_1") (pintype "passive"))
    )
    (net (code "9") (name "/CELL_V8") (class "Default")
      (node (ref "D9") (pin "1") (pinfunction "Anode_1") (pintype "passive"))
      (node (ref "Q9") (pin "2") (pinfunction "SOURCE_2") (pintype "passive"))
      (node (ref "R41") (pin "2") (pinfunction "2_2") (pintype "passive"))
      (node (ref "R9") (pin "1") (pinfunction "1_1") (pintype "passive"))
      (node (ref "TP12") (pin "1") (pinfunction "=value_1") (pintype "passive"))
    )
    (net (code "10") (name "/CELL_V9") (class "Default")
      (node (ref "D10") (pin "1") (pinfunction "Anode_1") (pintype "passive"))
      (node (ref "Q10") (pin "2") (pinfunction "SOURCE_2") (pintype "passive"))
      (node (ref "R10") (pin "1") (pinfunction "1_1") (pintype "passive"))
      (node (ref "R42") (pin "2") (pinfunction "2_2") (pintype "passive"))
      (node (ref "TP11") (pin "1") (pinfunction "=value_1") (pintype "passive"))
    )
    (net (code "11") (name "/CELL_V10") (class "Default")
      (node (ref "D11") (pin "1") (pinfunction "Anode_1") (pintype "passive"))
      (node (ref "Q11") (pin "2") (pinfunction "SOURCE_2") (pintype "passive"))
      (node (ref "R11") (pin "1") (pinfunction "1_1") (pintype "passive"))
      (node (ref "R43") (pin "2") (pinfunction "2_2") (pintype "passive"))
      (node (ref "TP10") (pin "1") (pinfunction "=value_1") (pintype "passive"))
    )
    (net (code "12") (name "/CELL_V11") (class "Default")
      (node (ref "D12") (pin "1") (pinfunction "Anode_1") (pintype "passive"))
      (node (ref "Q12") (pin "2") (pinfunction "SOURCE_2") (pintype "passive"))
      (node (ref "R12") (pin "1") (pinfunction "1_1") (pintype "passive"))
      (node (ref "R44") (pin "2") (pinfunction "2_2") (pintype "passive"))
      (node (ref "TP9") (pin "1") (pinfunction "=value_1") (pintype "passive"))
    )
    (net (code "13") (name "/CELL_V12") (class "Default")
      (node (ref "D16") (pin "1") (pinfunction "Anode_1") (pintype "passive"))
      (node (ref "Q18") (pin "2") (pinfunction "SOURCE_2") (pintype "passive"))
      (node (ref "R13") (pin "1") (pinfunction "1_1") (pintype "passive"))
      (node (ref "R45") (pin "2") (pinfunction "2_2") (pintype "passive"))
      (node (ref "TP8") (pin "1") (pinfunction "=value_1") (pintype "passive"))
    )
    (net (code "14") (name "/CELL_V13") (class "Default")
      (node (ref "D15") (pin "1") (pinfunction "Anode_1") (pintype "passive"))
      (node (ref "Q16") (pin "2") (pinfunction "SOURCE_2") (pintype "passive"))
      (node (ref "R60") (pin "1") (pinfunction "1_1") (pintype "passive"))
      (node (ref "R89") (pin "2") (pinfunction "2_2") (pintype "passive"))
      (node (ref "TP25") (pin "1") (pinfunction "=value_1") (pintype "passive"))
    )
    (net (code "15") (name "/CELL_V14") (class "Default")
      (node (ref "D14") (pin "1") (pinfunction "Anode_1") (pintype "passive"))
      (node (ref "Q15") (pin "2") (pinfunction "SOURCE_2") (pintype "passive"))
      (node (ref "R33") (pin "1") (pinfunction "1_1") (pintype "passive"))
      (node (ref "R48") (pin "2") (pinfunction "2_2") (pintype "passive"))
      (node (ref "TP16") (pin "1") (pinfunction "=value_1") (pintype "passive"))
    )
    (net (code "16") (name "/CELL_V15") (class "Default")
      (node (ref "D13") (pin "1") (pinfunction "Anode_1") (pintype "passive"))
      (node (ref "Q14") (pin "2") (pinfunction "SOURCE_2") (pintype "passive"))
      (node (ref "R30") (pin "1") (pinfunction "1_1") (pintype "passive"))
      (node (ref "R31") (pin "2") (pinfunction "2_2") (pintype "passive"))
      (node (ref "TP6") (pin "1") (pinfunction "=value_1") (pintype "passive"))
    )
    (net (code "17") (name "/CELL_V16") (class "Default")
      (node (ref "R15") (pin "1") (pinfunction "1_1") (pintype "passive"))
      (node (ref "R16") (pin "2") (pinfunction "2_2") (pintype "passive"))
      (node (ref "TP4") (pin "1") (pinfunction "=value_1") (pintype "passive"))
    )
    (net (code "19") (name "/VC0") (class "Default")
      (node (ref "C1") (pin "2") (pinfunction "2_2") (pintype "passive"))
      (node (ref "R1") (pin "2") (pinfunction "2_2") (pintype "passive"))
      (node (ref "R18") (pin "2") (pinfunction "2_2") (pintype "passive"))
      (node (ref "TP38") (pin "1") (pinfunction "=value_1") (pintype "passive"))
    )
    (net (code "20") (name "/VC1") (class "Default")
      (node (ref "C2") (pin "2") (pinfunction "2_2") (pintype "passive"))
      (node (ref "C3") (pin "1") (pinfunction "1_1") (pintype "passive"))
      (node (ref "R19") (pin "2") (pinfunction "2_2") (pintype "passive"))
      (node (ref "R2") (pin "2") (pinfunction "2_2") (pintype "passive"))
      (node (ref "TP37") (pin "1") (pinfunction "=value_1") (pintype "passive"))
    )
    (net (code "21") (name "/VC2") (class "Default")
      (node (ref "C3") (pin "2") (pinfunction "2_2") (pintype "passive"))
      (node (ref "C4") (pin "1") (pinfunction "1_1") (pintype "passive"))
      (node (ref "R20") (pin "2") (pinfunction "2_2") (pintype "passive"))
      (node (ref "R3") (pin "2") (pinfunction "2_2") (pintype "passive"))
      (node (ref "TP36") (pin "1") (pinfunction "=value_1") (pintype "passive"))
    )
    (net (code "22") (name "/VC3") (class "Default")
      (node (ref "C4") (pin "2") (pinfunction "2_2") (pintype "passive"))
      (node (ref "C5") (pin "1") (pinfunction "1_1") (pintype "passive"))
      (node (ref "R21") (pin "2") (pinfunction "2_2") (pintype "passive"))
      (node (ref "R4") (pin "2") (pinfunction "2_2") (pintype "passive"))
      (node (ref "TP35") (pin "1") (pinfunction "=value_1") (pintype "passive"))
    )
    (net (code "23") (name "/VC4") (class "Default")
      (node (ref "C5") (pin "2") (pinfunction "2_2") (pintype "passive"))
      (node (ref "C6") (pin "1") (pinfunction "1_1") (pintype "passive"))
      (node (ref "R22") (pin "2") (pinfunction "2_2") (pintype "passive"))
      (node (ref "R5") (pin "2") (pinfunction "2_2") (pintype "passive"))
      (node (ref "TP34") (pin "1") (pinfunction "=value_1") (pintype "passive"))
    )
    (net (code "24") (name "/VC5") (class "Default")
      (node (ref "C6") (pin "2") (pinfunction "2_2") (pintype "passive"))
      (node (ref "C7") (pin "1") (pinfunction "1_1") (pintype "passive"))
      (node (ref "R23") (pin "2") (pinfunction "2_2") (pintype "passive"))
      (node (ref "R6") (pin "2") (pinfunction "2_2") (pintype "passive"))
      (node (ref "TP33") (pin "1") (pinfunction "=value_1") (pintype "passive"))
    )
    (net (code "25") (name "/VC6") (class "Default")
      (node (ref "C7") (pin "2") (pinfunction "2_2") (pintype "passive"))
      (node (ref "C8") (pin "1") (pinfunction "1_1") (pintype "passive"))
      (node (ref "R24") (pin "2") (pinfunction "2_2") (pintype "passive"))
      (node (ref "R7") (pin "2") (pinfunction "2_2") (pintype "passive"))
      (node (ref "TP32") (pin "1") (pinfunction "=value_1") (pintype "passive"))
    )
    (net (code "26") (name "/VC7") (class "Default")
      (node (ref "C8") (pin "2") (pinfunction "2_2") (pintype "passive"))
      (node (ref "C9") (pin "1") (pinfunction "1_1") (pintype "passive"))
      (node (ref "R25") (pin "2") (pinfunction "2_2") (pintype "passive"))
      (node (ref "R8") (pin "2") (pinfunction "2_2") (pintype "passive"))
      (node (ref "TP31") (pin "1") (pinfunction "=value_1") (pintype "passive"))
    )
    (net (code "27") (name "/VC8") (class "Default")
      (node (ref "C10") (pin "1") (pinfunction "1_1") (pintype "passive"))
      (node (ref "C9") (pin "2") (pinfunction "2_2") (pintype "passive"))
      (node (ref "R26") (pin "2") (pinfunction "2_2") (pintype "passive"))
      (node (ref "R9") (pin "2") (pinfunction "2_2") (pintype "passive"))
      (node (ref "TP30") (pin "1") (pinfunction "=value_1") (pintype "passive"))
    )
    (net (code "28") (name "/VC9") (class "Default")
      (node (ref "C10") (pin "2") (pinfunction "2_2") (pintype "passive"))
      (node (ref "C11") (pin "1") (pinfunction "1_1") (pintype "passive"))
      (node (ref "R10") (pin "2") (pinfunction "2_2") (pintype "passive"))
      (node (ref "R27") (pin "2") (pinfunction "2_2") (pintype "passive"))
      (node (ref "TP29") (pin "1") (pinfunction "=value_1") (pintype "passive"))
    )
    (net (code "29") (name "/VC10") (class "Default")
      (node (ref "C11") (pin "2") (pinfunction "2_2") (pintype "passive"))
      (node (ref "C12") (pin "1") (pinfunction "1_1") (pintype "passive"))
      (node (ref "R11") (pin "2") (pinfunction "2_2") (pintype "passive"))
      (node (ref "R28") (pin "2") (pinfunction "2_2") (pintype "passive"))
      (node (ref "TP28") (pin "1") (pinfunction "=value_1") (pintype "passive"))
    )
    (net (code "30") (name "/VC11") (class "Default")
      (node (ref "C12") (pin "2") (pinfunction "2_2") (pintype "passive"))
      (node (ref "C13") (pin "1") (pinfunction "1_1") (pintype "passive"))
      (node (ref "R12") (pin "2") (pinfunction "2_2") (pintype "passive"))
      (node (ref "R29") (pin "2") (pinfunction "2_2") (pintype "passive"))
      (node (ref "TP27") (pin "1") (pinfunction "=value_1") (pintype "passive"))
    )
    (net (code "31") (name "/VC12") (class "Default")
      (node (ref "C13") (pin "2") (pinfunction "2_2") (pintype "passive"))
      (node (ref "C17") (pin "1") (pinfunction "1_1") (pintype "passive"))
      (node (ref "R103") (pin "2") (pinfunction "2_2") (pintype "passive"))
      (node (ref "R13") (pin "2") (pinfunction "2_2") (pintype "passive"))
      (node (ref "TP26") (pin "1") (pinfunction "=value_1") (pintype "passive"))
    )
    (net (code "32") (name "/VC13") (class "Default")
      (node (ref "C16") (pin "1") (pinfunction "1_1") (pintype "passive"))
      (node (ref "C17") (pin "2") (pinfunction "2_2") (pintype "passive"))
      (node (ref "R49") (pin "2") (pinfunction "2_2") (pintype "passive"))
      (node (ref "R60") (pin "2") (pinfunction "2_2") (pintype "passive"))
      (node (ref "TP62") (pin "1") (pinfunction "=value_1") (pintype "passive"))
    )
    (net (code "33") (name "/VC14") (class "Default")
      (node (ref "C15") (pin "1") (pinfunction "1_1") (pintype "passive"))
      (node (ref "C16") (pin "2") (pinfunction "2_2") (pintype "passive"))
      (node (ref "R32") (pin "2") (pinfunction "2_2") (pintype "passive"))
      (node (ref "R33") (pin "2") (pinfunction "2_2") (pintype "passive"))
      (node (ref "TP24") (pin "1") (pinfunction "=value_1") (pintype "passive"))
    )
    (net (code "34") (name "/VC15") (class "Default")
      (node (ref "C14") (pin "1") (pinfunction "1_1") (pintype "passive"))
      (node (ref "C15") (pin "2") (pinfunction "2_2") (pintype "passive"))
      (node (ref "R17") (pin "2") (pinfunction "2_2") (pintype "passive"))
      (node (ref "R30") (pin "2") (pinfunction "2_2") (pintype "passive"))
      (node (ref "TP7") (pin "1") (pinfunction "=value_1") (pintype "passive"))
    )
    (net (code "35") (name "/VC16") (class "Default")
      (node (ref "C14") (pin "2") (pinfunction "2_2") (pintype "passive"))
      (node (ref "R15") (pin "2") (pinfunction "2_2") (pintype "passive"))
      (node (ref "TP5") (pin "1") (pinfunction "=value_1") (pintype "passive"))
    )
    (net (code "37") (name "Net-(D1-Cathode)") (class "Default")
      (node (ref "D1") (pin "2") (pinfunction "Cathode_2") (pintype "passive"))
      (node (ref "Q1") (pin "1") (pinfunction "GATE_1") (pintype "passive"))
      (node (ref "R18") (pin "1") (pinfunction "1_1") (pintype "passive"))
    )
    (net (code "38") (name "Net-(D2-Cathode)") (class "Default")
      (node (ref "D2") (pin "2") (pinfunction "Cathode_2") (pintype "passive"))
      (node (ref "Q2") (pin "1") (pinfunction "GATE_1") (pintype "passive"))
      (node (ref "R19") (pin "1") (pinfunction "1_1") (pintype "passive"))
    )
    (net (code "39") (name "Net-(D3-Cathode)") (class "Default")
      (node (ref "D3") (pin "2") (pinfunction "Cathode_2") (pintype "passive"))
      (node (ref "Q3") (pin "1") (pinfunction "GATE_1") (pintype "passive"))
      (node (ref "R20") (pin "1") (pinfunction "1_1") (pintype "passive"))
    )
    (net (code "40") (name "Net-(D4-Cathode)") (class "Default")
      (node (ref "D4") (pin "2") (pinfunction "Cathode_2") (pintype "passive"))
      (node (ref "Q4") (pin "1") (pinfunction "GATE_1") (pintype "passive"))
      (node (ref "R21") (pin "1") (pinfunction "1_1") (pintype "passive"))
    )
    (net (code "41") (name "Net-(D5-Cathode)") (class "Default")
      (node (ref "D5") (pin "2") (pinfunction "Cathode_2") (pintype "passive"))
      (node (ref "Q5") (pin "1") (pinfunction "GATE_1") (pintype "passive"))
      (node (ref "R22") (pin "1") (pinfunction "1_1") (pintype "passive"))
    )
    (net (code "42") (name "Net-(D6-Cathode)") (class "Default")
      (node (ref "D6") (pin "2") (pinfunction "Cathode_2") (pintype "passive"))
      (node (ref "Q6") (pin "1") (pinfunction "GATE_1") (pintype "passive"))
      (node (ref "R23") (pin "1") (pinfunction "1_1") (pintype "passive"))
    )
    (net (code "43") (name "Net-(D7-Cathode)") (class "Default")
      (node (ref "D7") (pin "2") (pinfunction "Cathode_2") (pintype "passive"))
      (node (ref "Q7") (pin "1") (pinfunction "GATE_1") (pintype "passive"))
      (node (ref "R24") (pin "1") (pinfunction "1_1") (pintype "passive"))
    )
    (net (code "44") (name "Net-(D8-Cathode)") (class "Default")
      (node (ref "D8") (pin "2") (pinfunction "Cathode_2") (pintype "passive"))
      (node (ref "Q8") (pin "1") (pinfunction "GATE_1") (pintype "passive"))
      (node (ref "R25") (pin "1") (pinfunction "1_1") (pintype "passive"))
    )
    (net (code "45") (name "Net-(D9-Cathode)") (class "Default")
      (node (ref "D9") (pin "2") (pinfunction "Cathode_2") (pintype "passive"))
      (node (ref "Q9") (pin "1") (pinfunction "GATE_1") (pintype "passive"))
      (node (ref "R26") (pin "1") (pinfunction "1_1") (pintype "passive"))
    )
    (net (code "46") (name "Net-(D10-Cathode)") (class "Default")
      (node (ref "D10") (pin "2") (pinfunction "Cathode_2") (pintype "passive"))
      (node (ref "Q10") (pin "1") (pinfunction "GATE_1") (pintype "passive"))
      (node (ref "R27") (pin "1") (pinfunction "1_1") (pintype "passive"))
    )
    (net (code "47") (name "Net-(D11-Cathode)") (class "Default")
      (node (ref "D11") (pin "2") (pinfunction "Cathode_2") (pintype "passive"))
      (node (ref "Q11") (pin "1") (pinfunction "GATE_1") (pintype "passive"))
      (node (ref "R28") (pin "1") (pinfunction "1_1") (pintype "passive"))
    )
    (net (code "48") (name "Net-(D12-Cathode)") (class "Default")
      (node (ref "D12") (pin "2") (pinfunction "Cathode_2") (pintype "passive"))
      (node (ref "Q12") (pin "1") (pinfunction "GATE_1") (pintype "passive"))
      (node (ref "R29") (pin "1") (pinfunction "1_1") (pintype "passive"))
    )
    (net (code "49") (name "Net-(D13-Cathode)") (class "Default")
      (node (ref "D13") (pin "2") (pinfunction "Cathode_2") (pintype "passive"))
      (node (ref "Q14") (pin "1") (pinfunction "GATE_1") (pintype "passive"))
      (node (ref "R17") (pin "1") (pinfunction "1_1") (pintype "passive"))
    )
    (net (code "50") (name "Net-(D14-Cathode)") (class "Default")
      (node (ref "D14") (pin "2") (pinfunction "Cathode_2") (pintype "passive"))
      (node (ref "Q15") (pin "1") (pinfunction "GATE_1") (pintype "passive"))
      (node (ref "R32") (pin "1") (pinfunction "1_1") (pintype "passive"))
    )
    (net (code "51") (name "Net-(D15-Cathode)") (class "Default")
      (node (ref "D15") (pin "2") (pinfunction "Cathode_2") (pintype "passive"))
      (node (ref "Q16") (pin "1") (pinfunction "GATE_1") (pintype "passive"))
      (node (ref "R49") (pin "1") (pinfunction "1_1") (pintype "passive"))
    )
    (net (code "52") (name "Net-(D16-Cathode)") (class "Default")
      (node (ref "D16") (pin "2") (pinfunction "Cathode_2") (pintype "passive"))
      (node (ref "Q18") (pin "1") (pinfunction "GATE_1") (pintype "passive"))
      (node (ref "R103") (pin "1") (pinfunction "1_1") (pintype "passive"))
    )
    (net (code "53") (name "Net-(Q1-DRAIN)") (class "Default")
      (node (ref "Q1") (pin "3") (pinfunction "DRAIN_3") (pintype "passive"))
      (node (ref "R34") (pin "1") (pinfunction "1_1") (pintype "passive"))
    )
    (net (code "54") (name "Net-(Q2-DRAIN)") (class "Default")
      (node (ref "Q2") (pin "3") (pinfunction "DRAIN_3") (pintype "passive"))
      (node (ref "R35") (pin "1") (pinfunction "1_1") (pintype "passive"))
    )
    (net (code "55") (name "Net-(Q3-DRAIN)") (class "Default")
      (node (ref "Q3") (pin "3") (pinfunction "DRAIN_3") (pintype "passive"))
      (node (ref "R36") (pin "1") (pinfunction "1_1") (pintype "passive"))
    )
    (net (code "56") (name "Net-(Q4-DRAIN)") (class "Default")
      (node (ref "Q4") (pin "3") (pinfunction "DRAIN_3") (pintype "passive"))
      (node (ref "R37") (pin "1") (pinfunction "1_1") (pintype "passive"))
    )
    (net (code "57") (name "Net-(Q5-DRAIN)") (class "Default")
      (node (ref "Q5") (pin "3") (pinfunction "DRAIN_3") (pintype "passive"))
      (node (ref "R38") (pin "1") (pinfunction "1_1") (pintype "passive"))
    )
    (net (code "58") (name "Net-(Q6-DRAIN)") (class "Default")
      (node (ref "Q6") (pin "3") (pinfunction "DRAIN_3") (pintype "passive"))
      (node (ref "R39") (pin "1") (pinfunction "1_1") (pintype "passive"))
    )
    (net (code "59") (name "Net-(Q7-DRAIN)") (class "Default")
      (node (ref "Q7") (pin "3") (pinfunction "DRAIN_3") (pintype "passive"))
      (node (ref "R40") (pin "1") (pinfunction "1_1") (pintype "passive"))
    )
    (net (code "60") (name "Net-(Q8-DRAIN)") (class "Default")
      (node (ref "Q8") (pin "3") (pinfunction "DRAIN_3") (pintype "passive"))
      (node (ref "R41") (pin "1") (pinfunction "1_1") (pintype "passive"))
    )
    (net (code "61") (name "Net-(Q9-DRAIN)") (class "Default")
      (node (ref "Q9") (pin "3") (pinfunction "DRAIN_3") (pintype "passive"))
      (node (ref "R42") (pin "1") (pinfunction "1_1") (pintype "passive"))
    )
    (net (code "62") (name "Net-(Q10-DRAIN)") (class "Default")
      (node (ref "Q10") (pin "3") (pinfunction "DRAIN_3") (pintype "passive"))
      (node (ref "R43") (pin "1") (pinfunction "1_1") (pintype "passive"))
    )
    (net (code "63") (name "Net-(Q11-DRAIN)") (class "Default")
      (node (ref "Q11") (pin "3") (pinfunction "DRAIN_3") (pintype "passive"))
      (node (ref "R44") (pin "1") (pinfunction "1_1") (pintype "passive"))
    )
    (net (code "64") (name "Net-(Q12-DRAIN)") (class "Default")
      (node (ref "Q12") (pin "3") (pinfunction "DRAIN_3") (pintype "passive"))
      (node (ref "R45") (pin "1") (pinfunction "1_1") (pintype "passive"))
    )
    (net (code "65") (name "Net-(Q14-DRAIN)") (class "Default")
      (node (ref "Q14") (pin "3") (pinfunction "DRAIN_3") (pintype "passive"))
      (node (ref "R16") (pin "1") (pinfunction "1_1") (pintype "passive"))
    )
    (net (code "66") (name "Net-(Q15-DRAIN)") (class "Default")
      (node (ref "Q15") (pin "3") (pinfunction "DRAIN_3") (pintype "passive"))
      (node (ref "R31") (pin "1") (pinfunction "1_1") (pintype "passive"))
    )
    (net (code "67") (name "Net-(Q16-DRAIN)") (class "Default")
      (node (ref "Q16") (pin "3") (pinfunction "DRAIN_3") (pintype "passive"))
      (node (ref "R48") (pin "1") (pinfunction "1_1") (pintype "passive"))
    )
    (net (code "68") (name "Net-(Q18-DRAIN)") (class "Default")
      (node (ref "Q18") (pin "3") (pinfunction "DRAIN_3") (pintype "passive"))
      (node (ref "R89") (pin "1") (pinfunction "1_1") (pintype "passive"))
    )
    (net (code "69") (name "VBAT-") (class "Default")
      (node (ref "C1") (pin "1") (pinfunction "1_1") (pintype "passive"))
      (node (ref "C2") (pin "1") (pinfunction "1_1") (pintype "passive"))
    )
  )
)
